# usb.net
KiCad netlist of a schematic drawn in Altium Designer
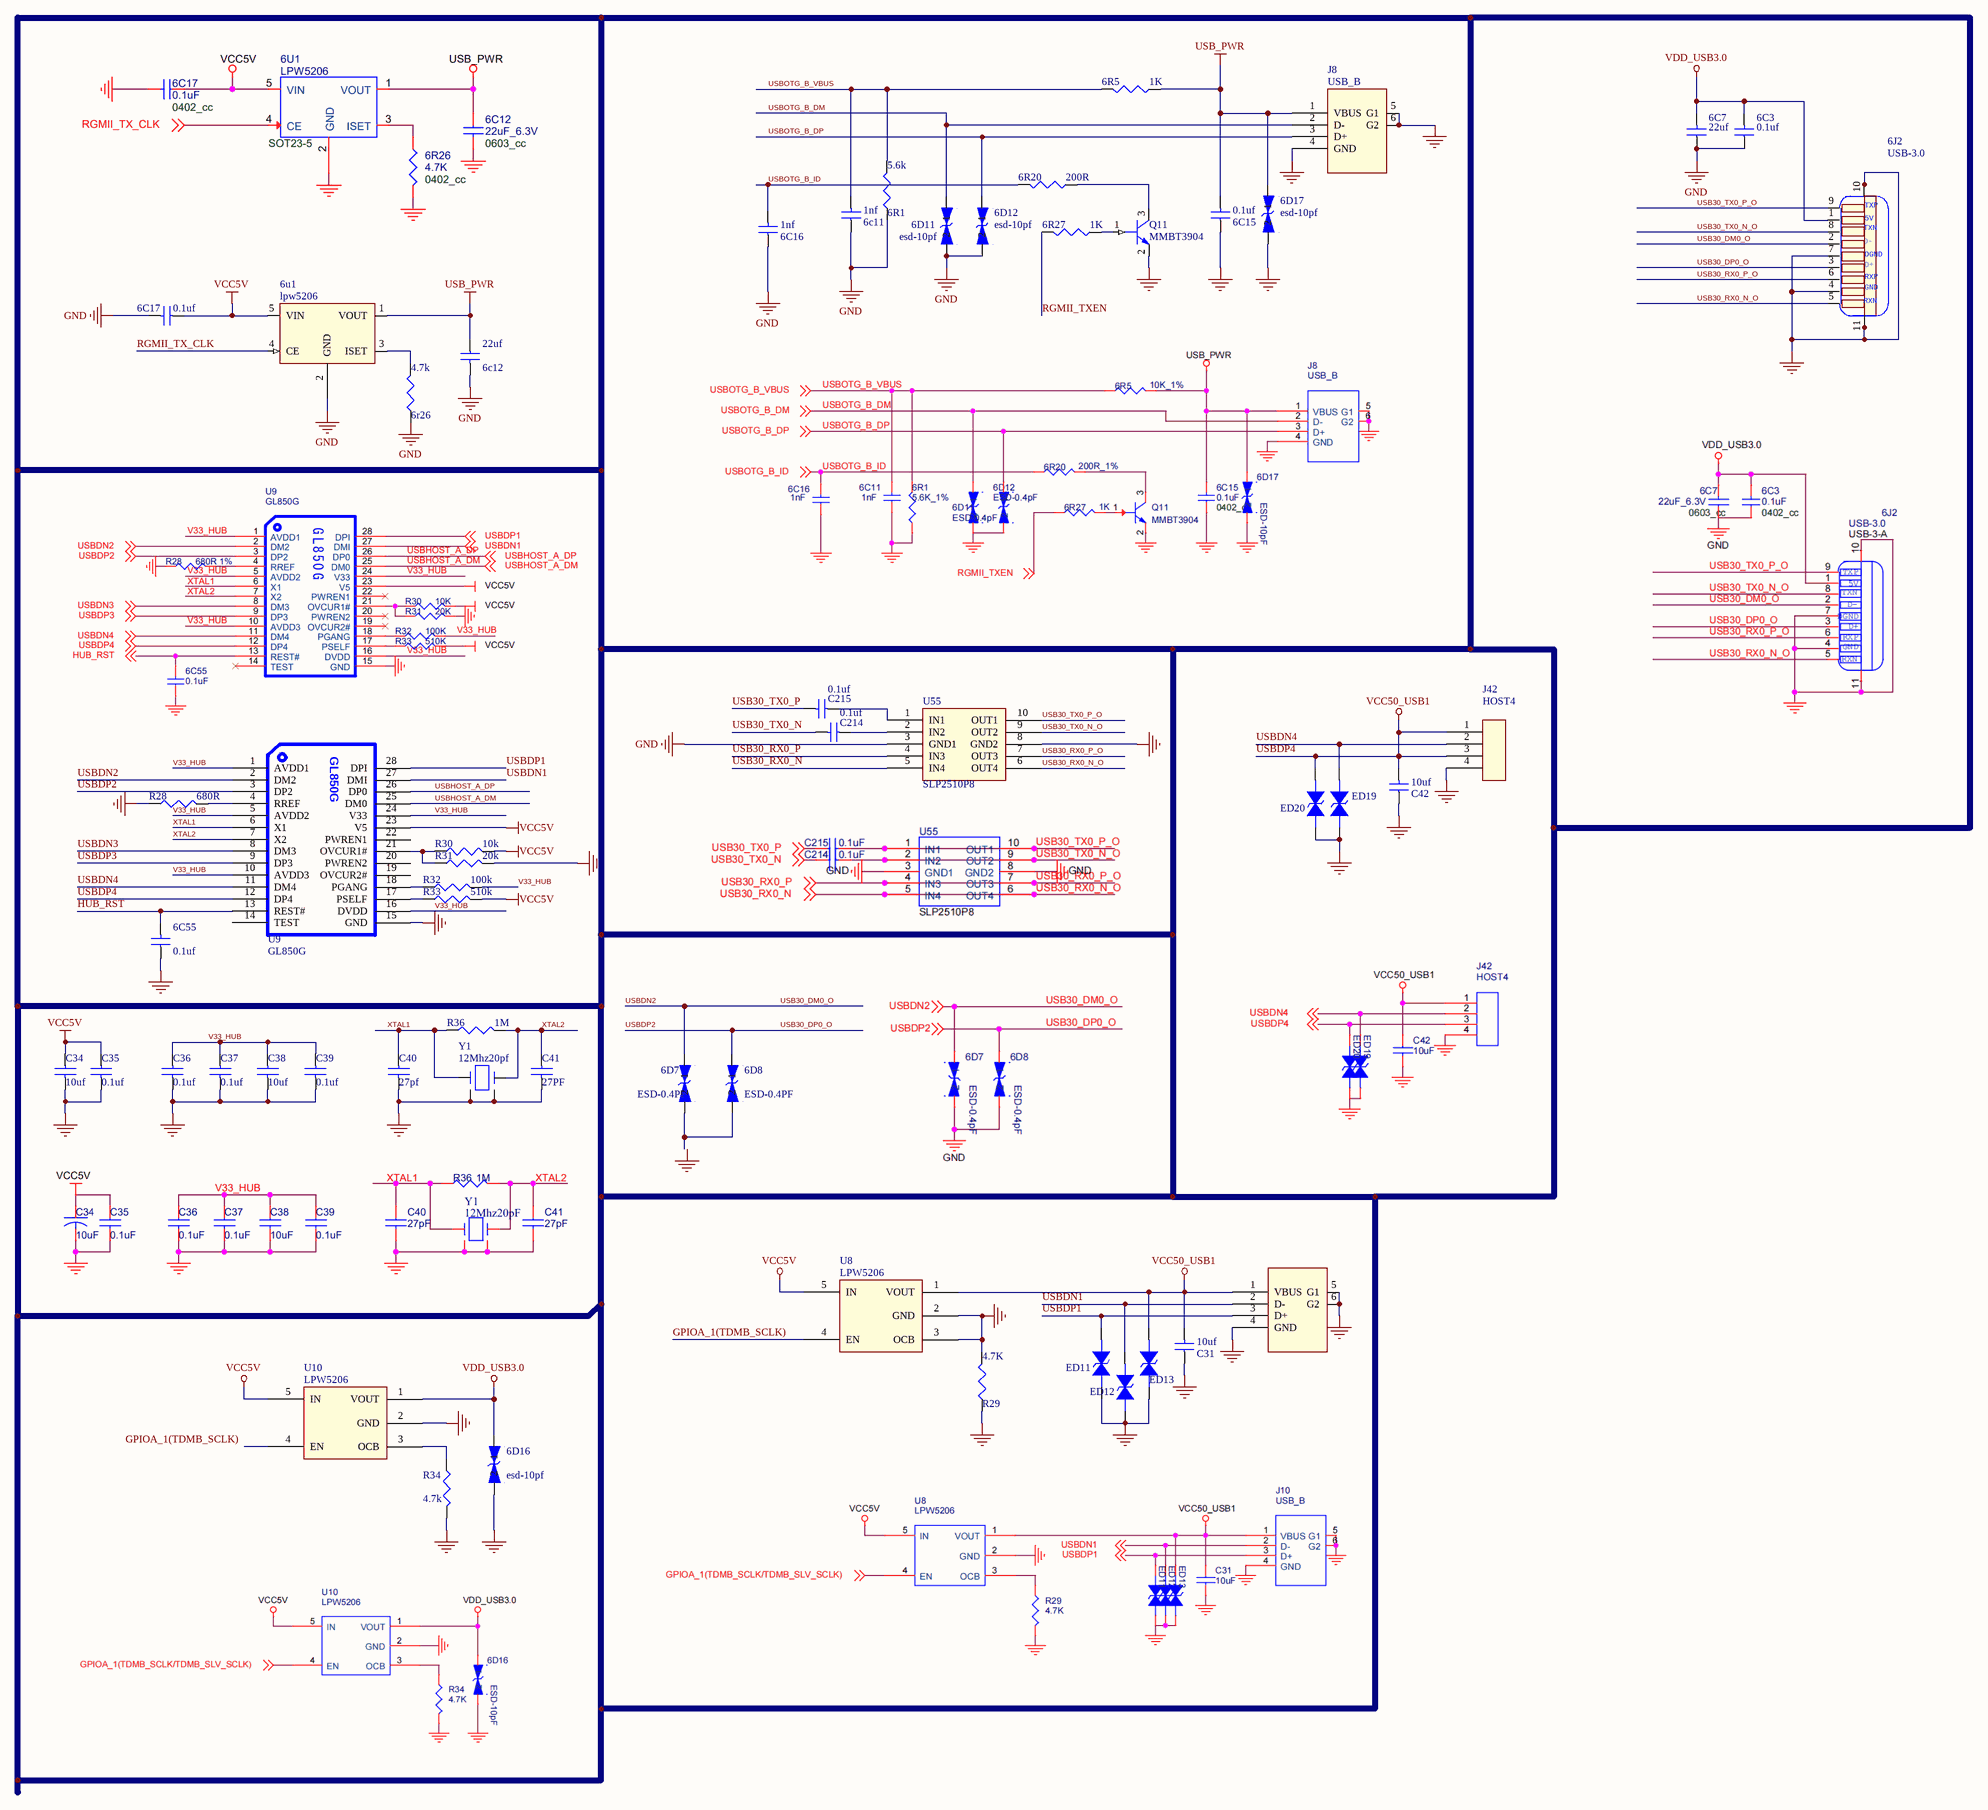
[diagram p0: usb.SchDoc]

(export (version "E")
  (design (tool "Eeschema 10.0.6"))
  (components
    (comp (ref "6C3") (value "0.1uf") (footprint "0603C") (libsource (lib "*") (part "capnp")))
    (comp (ref "6C7") (value "22uf") (footprint "0603C") (libsource (lib "*") (part "capnp")))
    (comp (ref "6c11") (value "1nf") (footprint "0603C") (libsource (lib "*") (part "capnp")))
    (comp (ref "6c12") (value "22uf") (footprint "0603C") (libsource (lib "*") (part "capnp")))
    (comp (ref "6C15") (value "0.1uf") (footprint "0603C") (libsource (lib "*") (part "capnp")))
    (comp (ref "6C16") (value "1nf") (footprint "0603C") (libsource (lib "*") (part "capnp")))
    (comp (ref "6C17") (value "0.1uf") (footprint "0603C") (libsource (lib "*") (part "capnp")))
    (comp (ref "6C55") (value "0.1uf") (footprint "0603C") (libsource (lib "*") (part "capnp")))
    (comp (ref "6D7") (value "ESD-0.4PF") (libsource (lib "*") (part "TVS DIODE")))
    (comp (ref "6D8") (value "ESD-0.4PF") (libsource (lib "*") (part "TVS DIODE")))
    (comp (ref "6D11") (value "esd-10pf") (libsource (lib "*") (part "TVS DIODE")))
    (comp (ref "6D12") (value "esd-10pf") (libsource (lib "*") (part "TVS DIODE")))
    (comp (ref "6D16") (value "esd-10pf") (libsource (lib "*") (part "TVS DIODE")))
    (comp (ref "6D17") (value "esd-10pf") (libsource (lib "*") (part "TVS DIODE")))
    (comp (ref "6J2") (value "USB-3.0") (libsource (lib "*") (part "USB_0")))
    (comp (ref "6R1") (value "5.6k") (footprint "R0603") (libsource (lib "*") (part "01RES")))
    (comp (ref "6R5") (value "1K") (footprint "R0603") (libsource (lib "*") (part "01RES")))
    (comp (ref "6R20") (value "200R") (footprint "R0603") (libsource (lib "*") (part "01RES")))
    (comp (ref "6r26") (value "4.7k") (footprint "R0603") (libsource (lib "*") (part "01RES")))
    (comp (ref "6R27") (value "1K") (footprint "R0603") (libsource (lib "*") (part "01RES")))
    (comp (ref "6u1") (value "lpw5206") (footprint "SOT-25") (libsource (lib "*") (part "U_RT9701_2")))
    (comp (ref "C31") (value "10uf") (footprint "0603C") (libsource (lib "*") (part "capnp")))
    (comp (ref "C34") (value "10uf") (libsource (lib "*") (part "CAP")))
    (comp (ref "C35") (value "0.1uf") (libsource (lib "*") (part "CAP")))
    (comp (ref "C36") (value "0.1uf") (libsource (lib "*") (part "CAP")))
    (comp (ref "C37") (value "0.1uf") (libsource (lib "*") (part "CAP")))
    (comp (ref "C38") (value "10uf") (libsource (lib "*") (part "CAP")))
    (comp (ref "C39") (value "0.1uf") (libsource (lib "*") (part "CAP")))
    (comp (ref "C40") (value "27pf") (libsource (lib "*") (part "CAP")))
    (comp (ref "C41") (value "27PF") (libsource (lib "*") (part "CAP")))
    (comp (ref "C42") (value "10uf") (footprint "0603C") (libsource (lib "*") (part "capnp")))
    (comp (ref "C214") (value "0.1uf") (footprint "0603C") (libsource (lib "*") (part "capnp")))
    (comp (ref "C215") (value "0.1uf") (footprint "0603C") (libsource (lib "*") (part "capnp")))
    (comp (ref "ED11") (value "~") (libsource (lib "*") (part "DIODE BI-DIR TRIG")))
    (comp (ref "ED12") (value "~") (libsource (lib "*") (part "DIODE BI-DIR TRIG")))
    (comp (ref "ED13") (value "~") (libsource (lib "*") (part "DIODE BI-DIR TRIG")))
    (comp (ref "ED19") (value "~") (libsource (lib "*") (part "DIODE BI-DIR TRIG")))
    (comp (ref "ED20") (value "~") (libsource (lib "*") (part "DIODE BI-DIR TRIG")))
    (comp (ref "J4") (value "~") (libsource (lib "*") (part "USB_A_1")))
    (comp (ref "J8") (value "USB_B") (libsource (lib "*") (part "USB_A_1")))
    (comp (ref "J42") (value "HOST4") (libsource (lib "*") (part "CON4")))
    (comp (ref "Q11") (value "MMBT3904") (libsource (lib "*") (part "NPN_1")))
    (comp (ref "R28") (value "680R") (footprint "R0603") (libsource (lib "*") (part "01RES")))
    (comp (ref "R29") (value "4.7K") (footprint "R0603") (libsource (lib "*") (part "01RES")))
    (comp (ref "R30") (value "10k") (footprint "R0603") (libsource (lib "*") (part "01RES")))
    (comp (ref "R31") (value "20k") (footprint "R0603") (libsource (lib "*") (part "01RES")))
    (comp (ref "R32") (value "100k") (footprint "R0603") (libsource (lib "*") (part "01RES")))
    (comp (ref "R33") (value "510k") (footprint "R0603") (libsource (lib "*") (part "01RES")))
    (comp (ref "R34") (value "4.7k") (footprint "R0402") (libsource (lib "*") (part "RESISTOR_2")))
    (comp (ref "R36") (value "1M") (footprint "R0603") (libsource (lib "*") (part "01RES")))
    (comp (ref "U8") (value "LPW5206") (libsource (lib "*") (part "SWITCH_SY6280")))
    (comp (ref "U9") (value "GL850G") (libsource (lib "*") (part "gl850_0")))
    (comp (ref "U10") (value "LPW5206") (libsource (lib "*") (part "SWITCH_SY6280")))
    (comp (ref "U55") (value "SLP2510P8") (libsource (lib "*") (part "rRClamp0524P")))
    (comp (ref "Y1") (value "12Mhz20pf") (libsource (lib "*") (part "CRYSTAL_2")))
  )
  (nets
    (net (code "1") (name "/GPIOA_1(TDMB_SCLK)") (class "Default")
      (node (ref "U8") (pin "4") (pinfunction "EN_4") (pintype "passive"))
    )
    (net (code "2") (name "/HUB_RST") (class "Default")
      (node (ref "6C55") (pin "2") (pinfunction "2_2") (pintype "passive"))
      (node (ref "U9") (pin "13") (pinfunction "REST#_13") (pintype "passive"))
    )
    (net (code "3") (name "/RGMII_TXEN") (class "Default")
      (node (ref "6R27") (pin "2") (pinfunction "2_2") (pintype "passive"))
    )
    (net (code "4") (name "/RGMII_TX_CLK") (class "Default")
      (node (ref "6u1") (pin "4") (pinfunction "CE_4") (pintype "input"))
    )
    (net (code "5") (name "/USB30_DM0_O") (class "Default")
      (node (ref "6D7") (pin "1") (pinfunction "1_1") (pintype "passive"))
      (node (ref "6J2") (pin "2") (pinfunction "D-_2") (pintype "passive"))
      (node (ref "U9") (pin "2") (pinfunction "DM2_2") (pintype "passive"))
    )
    (net (code "6") (name "/USB30_DP0_O") (class "Default")
      (node (ref "6D8") (pin "1") (pinfunction "1_1") (pintype "passive"))
      (node (ref "6J2") (pin "3") (pinfunction "D+_3") (pintype "passive"))
      (node (ref "U9") (pin "3") (pinfunction "DP2_3") (pintype "passive"))
    )
    (net (code "7") (name "/USB30_RX0_N") (class "Default")
      (node (ref "U55") (pin "5") (pinfunction "IN4_5") (pintype "passive"))
    )
    (net (code "8") (name "/USB30_RX0_N_O") (class "Default")
      (node (ref "6J2") (pin "5") (pinfunction "RXN_5") (pintype "passive"))
      (node (ref "U55") (pin "6") (pinfunction "OUT4_6") (pintype "passive"))
    )
    (net (code "9") (name "/USB30_RX0_P") (class "Default")
      (node (ref "U55") (pin "4") (pinfunction "IN3_4") (pintype "passive"))
    )
    (net (code "10") (name "/USB30_RX0_P_O") (class "Default")
      (node (ref "6J2") (pin "6") (pinfunction "RXP_6") (pintype "passive"))
      (node (ref "U55") (pin "7") (pinfunction "OUT3_7") (pintype "passive"))
    )
    (net (code "11") (name "/USB30_TX0_N") (class "Default")
      (node (ref "C214") (pin "2") (pinfunction "2_2") (pintype "passive"))
    )
    (net (code "12") (name "/USB30_TX0_N_O") (class "Default")
      (node (ref "6J2") (pin "8") (pinfunction "TXN_8") (pintype "passive"))
      (node (ref "U55") (pin "9") (pinfunction "OUT2_9") (pintype "passive"))
    )
    (net (code "13") (name "/USB30_TX0_P") (class "Default")
      (node (ref "C215") (pin "2") (pinfunction "2_2") (pintype "passive"))
    )
    (net (code "14") (name "/USB30_TX0_P_O") (class "Default")
      (node (ref "6J2") (pin "9") (pinfunction "TXP_9") (pintype "passive"))
      (node (ref "U55") (pin "10") (pinfunction "OUT1_10") (pintype "passive"))
    )
    (net (code "15") (name "/USBDN1") (class "Default")
      (node (ref "ED12") (pin "1") (pinfunction "1_1") (pintype "passive"))
      (node (ref "J4") (pin "2") (pinfunction "D-_2") (pintype "passive"))
      (node (ref "U9") (pin "27") (pinfunction "DMI_27") (pintype "passive"))
    )
    (net (code "16") (name "/USBDN3") (class "Default")
      (node (ref "U9") (pin "8") (pinfunction "DM3_8") (pintype "passive"))
    )
    (net (code "17") (name "/USBDN4") (class "Default")
      (node (ref "ED19") (pin "1") (pinfunction "1_1") (pintype "passive"))
      (node (ref "J42") (pin "2") (pinfunction "2_2") (pintype "passive"))
      (node (ref "U9") (pin "11") (pinfunction "DM4_11") (pintype "passive"))
    )
    (net (code "18") (name "/USBDP1") (class "Default")
      (node (ref "ED11") (pin "1") (pinfunction "1_1") (pintype "passive"))
      (node (ref "J4") (pin "3") (pinfunction "D+_3") (pintype "passive"))
      (node (ref "U9") (pin "28") (pinfunction "DPI_28") (pintype "passive"))
    )
    (net (code "19") (name "/USBDP3") (class "Default")
      (node (ref "U9") (pin "9") (pinfunction "DP3_9") (pintype "passive"))
    )
    (net (code "20") (name "/USBHOST_A_DM") (class "Default")
      (node (ref "U9") (pin "25") (pinfunction "DM0_25") (pintype "passive"))
    )
    (net (code "21") (name "/USBHOST_A_DP") (class "Default")
      (node (ref "U9") (pin "26") (pinfunction "DP0_26") (pintype "passive"))
    )
    (net (code "22") (name "/USBOTG_B_DM") (class "Default")
      (node (ref "6D11") (pin "1") (pinfunction "1_1") (pintype "passive"))
      (node (ref "J8") (pin "2") (pinfunction "D-_2") (pintype "passive"))
    )
    (net (code "23") (name "/USBOTG_B_DP") (class "Default")
      (node (ref "6D12") (pin "1") (pinfunction "1_1") (pintype "passive"))
      (node (ref "J8") (pin "3") (pinfunction "D+_3") (pintype "passive"))
    )
    (net (code "24") (name "/USBOTG_B_ID") (class "Default")
      (node (ref "6C16") (pin "2") (pinfunction "2_2") (pintype "passive"))
      (node (ref "6R20") (pin "2") (pinfunction "2_2") (pintype "passive"))
    )
    (net (code "25") (name "/USBOTG_B_VBUS") (class "Default")
      (node (ref "6R1") (pin "2") (pinfunction "2_2") (pintype "passive"))
      (node (ref "6R5") (pin "2") (pinfunction "2_2") (pintype "passive"))
      (node (ref "6c11") (pin "2") (pinfunction "2_2") (pintype "passive"))
    )
    (net (code "26") (name "/V33_HUB") (class "Default")
      (node (ref "C36") (pin "1") (pinfunction "1_1") (pintype "passive"))
      (node (ref "C37") (pin "1") (pinfunction "1_1") (pintype "passive"))
      (node (ref "C38") (pin "1") (pinfunction "1_1") (pintype "passive"))
      (node (ref "C39") (pin "1") (pinfunction "1_1") (pintype "passive"))
      (node (ref "R32") (pin "2") (pinfunction "2_2") (pintype "passive"))
      (node (ref "U9") (pin "1") (pinfunction "AVDD1_1") (pintype "passive"))
      (node (ref "U9") (pin "10") (pinfunction "AVDD3_10") (pintype "passive"))
      (node (ref "U9") (pin "16") (pinfunction "DVDD_16") (pintype "passive"))
      (node (ref "U9") (pin "24") (pinfunction "V33_24") (pintype "passive"))
      (node (ref "U9") (pin "5") (pinfunction "AVDD2_5") (pintype "passive"))
    )
    (net (code "27") (name "/XTAL1") (class "Default")
      (node (ref "C40") (pin "1") (pinfunction "1_1") (pintype "passive"))
      (node (ref "R36") (pin "1") (pinfunction "1_1") (pintype "passive"))
      (node (ref "U9") (pin "6") (pinfunction "X1_6") (pintype "passive"))
      (node (ref "Y1") (pin "1") (pinfunction "1_1") (pintype "passive"))
    )
    (net (code "28") (name "/XTAL2") (class "Default")
      (node (ref "C41") (pin "1") (pinfunction "1_1") (pintype "passive"))
      (node (ref "R36") (pin "2") (pinfunction "2_2") (pintype "passive"))
      (node (ref "U9") (pin "7") (pinfunction "X2_7") (pintype "passive"))
      (node (ref "Y1") (pin "3") (pinfunction "3_3") (pintype "passive"))
    )
    (net (code "29") (name "<NO NET>") (class "Default")
      (node (ref "6C15") (pin "1") (pinfunction "1_1") (pintype "passive"))
      (node (ref "6C55") (pin "1") (pinfunction "1_1") (pintype "passive"))
      (node (ref "6D16") (pin "2") (pinfunction "2_2") (pintype "passive"))
      (node (ref "6D17") (pin "2") (pinfunction "2_2") (pintype "passive"))
      (node (ref "6J2") (pin "10") (pinfunction "S1_10") (pintype "passive"))
      (node (ref "6J2") (pin "11") (pinfunction "S2_11") (pintype "passive"))
      (node (ref "6J2") (pin "4") (pinfunction "GND_4") (pintype "passive"))
      (node (ref "6J2") (pin "7") (pinfunction "DGND_7") (pintype "passive"))
      (node (ref "C31") (pin "1") (pinfunction "1_1") (pintype "passive"))
      (node (ref "C34") (pin "2") (pinfunction "2_2") (pintype "passive"))
      (node (ref "C35") (pin "2") (pinfunction "2_2") (pintype "passive"))
      (node (ref "C36") (pin "2") (pinfunction "2_2") (pintype "passive"))
      (node (ref "C37") (pin "2") (pinfunction "2_2") (pintype "passive"))
      (node (ref "C38") (pin "2") (pinfunction "2_2") (pintype "passive"))
      (node (ref "C39") (pin "2") (pinfunction "2_2") (pintype "passive"))
      (node (ref "C40") (pin "2") (pinfunction "2_2") (pintype "passive"))
      (node (ref "C41") (pin "2") (pinfunction "2_2") (pintype "passive"))
      (node (ref "C42") (pin "1") (pinfunction "1_1") (pintype "passive"))
      (node (ref "ED11") (pin "2") (pinfunction "2_2") (pintype "passive"))
      (node (ref "ED12") (pin "2") (pinfunction "2_2") (pintype "passive"))
      (node (ref "ED13") (pin "2") (pinfunction "2_2") (pintype "passive"))
      (node (ref "ED19") (pin "2") (pinfunction "2_2") (pintype "passive"))
      (node (ref "ED20") (pin "2") (pinfunction "2_2") (pintype "passive"))
      (node (ref "J4") (pin "4") (pinfunction "GND_4") (pintype "passive"))
      (node (ref "J4") (pin "5") (pinfunction "G1_5") (pintype "passive"))
      (node (ref "J4") (pin "6") (pinfunction "G2_6") (pintype "passive"))
      (node (ref "J42") (pin "4") (pinfunction "4_4") (pintype "passive"))
      (node (ref "J8") (pin "4") (pinfunction "GND_4") (pintype "passive"))
      (node (ref "J8") (pin "5") (pinfunction "G1_5") (pintype "passive"))
      (node (ref "J8") (pin "6") (pinfunction "G2_6") (pintype "passive"))
      (node (ref "Q11") (pin "2") (pinfunction "EMITTER_2") (pintype "passive"))
      (node (ref "R28") (pin "1") (pinfunction "1_1") (pintype "passive"))
      (node (ref "R29") (pin "1") (pinfunction "1_1") (pintype "passive"))
      (node (ref "R29") (pin "2") (pinfunction "2_2") (pintype "passive"))
      (node (ref "R31") (pin "2") (pinfunction "2_2") (pintype "passive"))
      (node (ref "R34") (pin "2") (pinfunction "2_2") (pintype "passive"))
      (node (ref "U10") (pin "2") (pinfunction "GND_2") (pintype "passive"))
      (node (ref "U55") (pin "8") (pinfunction "GND2_8") (pintype "passive"))
      (node (ref "U8") (pin "2") (pinfunction "GND_2") (pintype "passive"))
      (node (ref "U8") (pin "3") (pinfunction "OCB_3") (pintype "passive"))
      (node (ref "U9") (pin "15") (pinfunction "GND_15") (pintype "passive"))
      (node (ref "Y1") (pin "2") (pinfunction "2_2") (pintype "passive"))
      (node (ref "Y1") (pin "4") (pinfunction "4_4") (pintype "passive"))
    )
    (net (code "30") (name "GND") (class "Default")
      (node (ref "6C16") (pin "1") (pinfunction "1_1") (pintype "passive"))
      (node (ref "6C17") (pin "2") (pinfunction "2_2") (pintype "passive"))
      (node (ref "6C3") (pin "1") (pinfunction "1_1") (pintype "passive"))
      (node (ref "6C7") (pin "1") (pinfunction "1_1") (pintype "passive"))
      (node (ref "6D11") (pin "2") (pinfunction "2_2") (pintype "passive"))
      (node (ref "6D12") (pin "2") (pinfunction "2_2") (pintype "passive"))
      (node (ref "6R1") (pin "1") (pinfunction "1_1") (pintype "passive"))
      (node (ref "6c11") (pin "1") (pinfunction "1_1") (pintype "passive"))
      (node (ref "6c12") (pin "2") (pinfunction "2_2") (pintype "passive"))
      (node (ref "6r26") (pin "1") (pinfunction "1_1") (pintype "passive"))
      (node (ref "6u1") (pin "2") (pinfunction "GND_2") (pintype "power_in"))
      (node (ref "U55") (pin "3") (pinfunction "GND1_3") (pintype "passive"))
    )
    (net (code "31") (name "Net-(6D7-Pad2)") (class "Default")
      (node (ref "6D7") (pin "2") (pinfunction "2_2") (pintype "passive"))
      (node (ref "6D8") (pin "2") (pinfunction "2_2") (pintype "passive"))
    )
    (net (code "32") (name "Net-(6u1-ISET)") (class "Default")
      (node (ref "6r26") (pin "2") (pinfunction "2_2") (pintype "passive"))
      (node (ref "6u1") (pin "3") (pinfunction "ISET_3") (pintype "open_collector"))
    )
    (net (code "33") (name "Net-(Q11-BASE)") (class "Default")
      (node (ref "6R27") (pin "1") (pinfunction "1_1") (pintype "passive"))
      (node (ref "Q11") (pin "1") (pinfunction "BASE_1") (pintype "input"))
    )
    (net (code "34") (name "Net-(Q11-COLLECT)") (class "Default")
      (node (ref "6R20") (pin "1") (pinfunction "1_1") (pintype "passive"))
      (node (ref "Q11") (pin "3") (pinfunction "COLLECT_3") (pintype "passive"))
    )
    (net (code "35") (name "Net-(U9-OVCUR1#)") (class "Default")
      (node (ref "R30") (pin "1") (pinfunction "1_1") (pintype "passive"))
      (node (ref "R31") (pin "1") (pinfunction "1_1") (pintype "passive"))
      (node (ref "U9") (pin "21") (pinfunction "OVCUR1#_21") (pintype "passive"))
    )
    (net (code "36") (name "Net-(U9-PGANG)") (class "Default")
      (node (ref "R32") (pin "1") (pinfunction "1_1") (pintype "passive"))
      (node (ref "U9") (pin "18") (pinfunction "PGANG_18") (pintype "passive"))
    )
    (net (code "37") (name "Net-(U9-PSELF)") (class "Default")
      (node (ref "R33") (pin "1") (pinfunction "1_1") (pintype "passive"))
      (node (ref "U9") (pin "17") (pinfunction "PSELF_17") (pintype "passive"))
    )
    (net (code "38") (name "Net-(U9-RREF)") (class "Default")
      (node (ref "R28") (pin "2") (pinfunction "2_2") (pintype "passive"))
      (node (ref "U9") (pin "4") (pinfunction "RREF_4") (pintype "passive"))
    )
    (net (code "39") (name "Net-(U10-OCB)") (class "Default")
      (node (ref "R34") (pin "1") (pinfunction "1_1") (pintype "passive"))
      (node (ref "U10") (pin "3") (pinfunction "OCB_3") (pintype "passive"))
    )
    (net (code "40") (name "Net-(U55-IN1)") (class "Default")
      (node (ref "C215") (pin "1") (pinfunction "1_1") (pintype "passive"))
      (node (ref "U55") (pin "1") (pinfunction "IN1_1") (pintype "passive"))
    )
    (net (code "41") (name "Net-(U55-IN2)") (class "Default")
      (node (ref "C214") (pin "1") (pinfunction "1_1") (pintype "passive"))
      (node (ref "U55") (pin "2") (pinfunction "IN2_2") (pintype "passive"))
    )
    (net (code "42") (name "USB_PWR") (class "Default")
      (node (ref "6C15") (pin "2") (pinfunction "2_2") (pintype "passive"))
      (node (ref "6D17") (pin "1") (pinfunction "1_1") (pintype "passive"))
      (node (ref "6R5") (pin "1") (pinfunction "1_1") (pintype "passive"))
      (node (ref "6c12") (pin "1") (pinfunction "1_1") (pintype "passive"))
      (node (ref "6u1") (pin "1") (pinfunction "VOUT_1") (pintype "power_in"))
      (node (ref "J8") (pin "1") (pinfunction "VBUS_1") (pintype "passive"))
    )
    (net (code "43") (name "VCC5V") (class "Default")
      (node (ref "6C17") (pin "1") (pinfunction "1_1") (pintype "passive"))
      (node (ref "6u1") (pin "5") (pinfunction "VIN_5") (pintype "power_in"))
      (node (ref "C34") (pin "1") (pinfunction "1_1") (pintype "passive"))
      (node (ref "C35") (pin "1") (pinfunction "1_1") (pintype "passive"))
      (node (ref "R30") (pin "2") (pinfunction "2_2") (pintype "passive"))
      (node (ref "R33") (pin "2") (pinfunction "2_2") (pintype "passive"))
      (node (ref "U10") (pin "5") (pinfunction "IN_5") (pintype "passive"))
      (node (ref "U8") (pin "5") (pinfunction "IN_5") (pintype "passive"))
      (node (ref "U9") (pin "23") (pinfunction "V5_23") (pintype "passive"))
    )
    (net (code "44") (name "VCC50_USB1") (class "Default")
      (node (ref "C31") (pin "2") (pinfunction "2_2") (pintype "passive"))
      (node (ref "C42") (pin "2") (pinfunction "2_2") (pintype "passive"))
      (node (ref "ED13") (pin "1") (pinfunction "1_1") (pintype "passive"))
      (node (ref "ED20") (pin "1") (pinfunction "1_1") (pintype "passive"))
      (node (ref "J4") (pin "1") (pinfunction "VBUS_1") (pintype "passive"))
      (node (ref "J42") (pin "1") (pinfunction "1_1") (pintype "passive"))
      (node (ref "J42") (pin "3") (pinfunction "3_3") (pintype "passive"))
      (node (ref "U8") (pin "1") (pinfunction "VOUT_1") (pintype "passive"))
      (node (ref "U9") (pin "12") (pinfunction "DP4_12") (pintype "passive"))
    )
    (net (code "45") (name "VDD_USB3.0") (class "Default")
      (node (ref "6C3") (pin "2") (pinfunction "2_2") (pintype "passive"))
      (node (ref "6C7") (pin "2") (pinfunction "2_2") (pintype "passive"))
      (node (ref "6D16") (pin "1") (pinfunction "1_1") (pintype "passive"))
      (node (ref "6J2") (pin "1") (pinfunction "VBUS_1") (pintype "passive"))
      (node (ref "U10") (pin "1") (pinfunction "VOUT_1") (pintype "passive"))
    )
    (net (code "46") (name "unconnected-(U9-OVCUR2#-Pad19)") (class "Default")
      (node (ref "U9") (pin "19") (pinfunction "OVCUR2#_19") (pintype "passive"))
    )
    (net (code "47") (name "unconnected-(U9-PWREN1-Pad22)") (class "Default")
      (node (ref "U9") (pin "22") (pinfunction "PWREN1_22") (pintype "passive"))
    )
    (net (code "48") (name "unconnected-(U9-PWREN2-Pad20)") (class "Default")
      (node (ref "U9") (pin "20") (pinfunction "PWREN2_20") (pintype "passive"))
    )
    (net (code "49") (name "unconnected-(U9-TEST-Pad14)") (class "Default")
      (node (ref "U9") (pin "14") (pinfunction "TEST_14") (pintype "passive"))
    )
    (net (code "50") (name "unconnected-(U10-EN-Pad4)") (class "Default")
      (node (ref "U10") (pin "4") (pinfunction "EN_4") (pintype "passive"))
    )
  )
)
